# Insperino_-_Ver_1_0.net
KiCad netlist of a schematic drawn in EAGLE
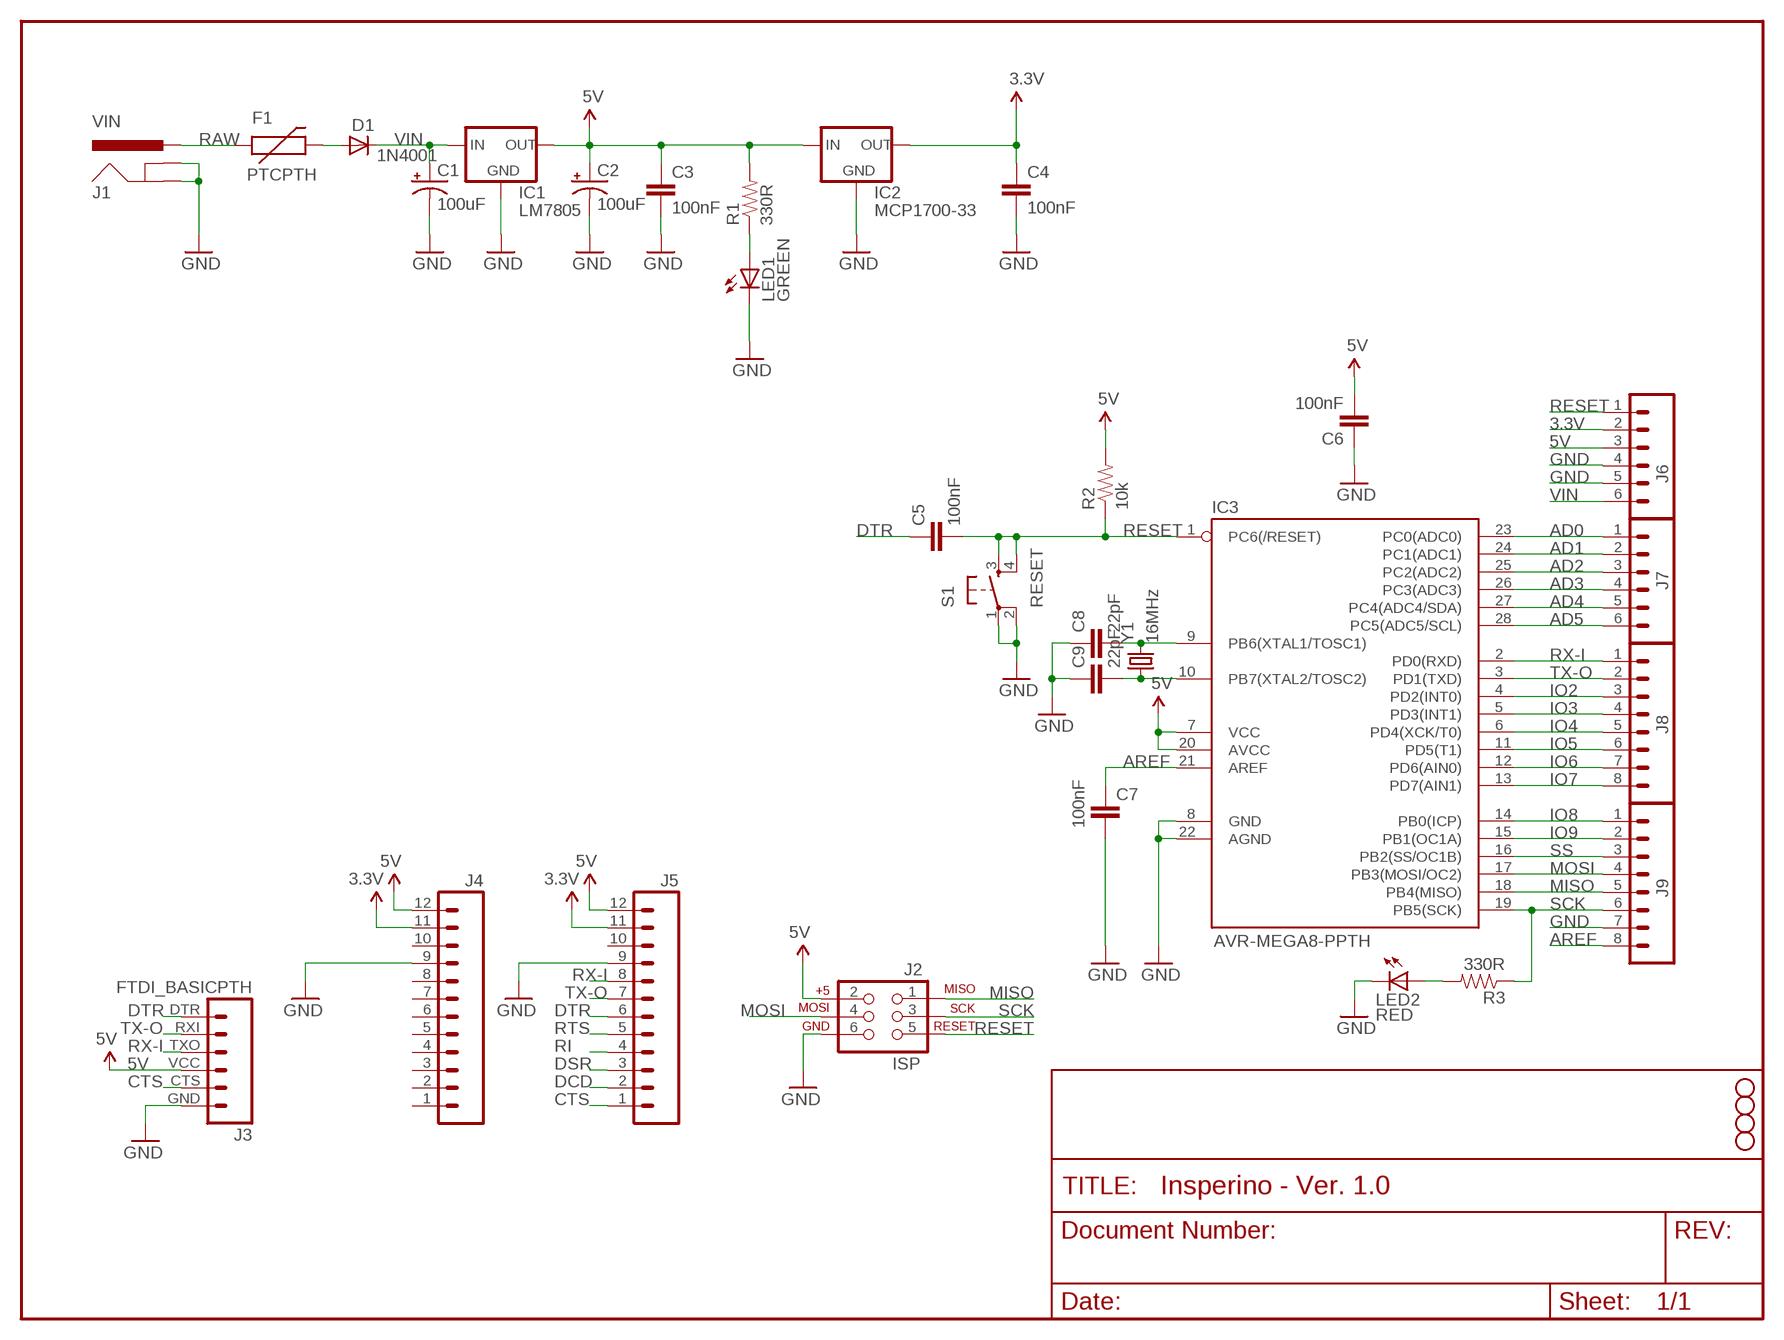
[diagram p0: schematic, sheet 1]

(export (version "E")
  (design (tool "Eeschema 10.0.6"))
  (components
    (comp (ref "C1")
      (value "100uF")
      (footprint "eagle-import:CPOL-RADIAL-100UF-25V")
      (libsource (lib "eagle-import") (part "CAP_POLPTH1"))
    )
    (comp (ref "C2")
      (value "100uF")
      (footprint "eagle-import:CPOL-RADIAL-100UF-25V")
      (libsource (lib "eagle-import") (part "CAP_POLPTH1"))
    )
    (comp (ref "C3")
      (value "100nF")
      (footprint "eagle-import:CAP-PTH-SMALL2")
      (libsource (lib "eagle-import") (part "CAPPTH2"))
    )
    (comp (ref "C4")
      (value "100nF")
      (footprint "eagle-import:CAP-PTH-SMALL2")
      (libsource (lib "eagle-import") (part "CAPPTH2"))
    )
    (comp (ref "C5")
      (value "100nF")
      (footprint "eagle-import:CAP-PTH-SMALL2")
      (libsource (lib "eagle-import") (part "CAPPTH2"))
    )
    (comp (ref "C6")
      (value "100nF")
      (footprint "eagle-import:CAP-PTH-SMALL2")
      (libsource (lib "eagle-import") (part "CAPPTH2"))
    )
    (comp (ref "C7")
      (value "100nF")
      (footprint "eagle-import:CAP-PTH-SMALL2")
      (libsource (lib "eagle-import") (part "CAPPTH2"))
    )
    (comp (ref "C8")
      (value "22pF")
      (footprint "eagle-import:CAP-PTH-SMALL2")
      (libsource (lib "eagle-import") (part "CAPPTH2"))
    )
    (comp (ref "C9")
      (value "22pF")
      (footprint "eagle-import:CAP-PTH-SMALL2")
      (libsource (lib "eagle-import") (part "CAPPTH2"))
    )
    (comp (ref "D1")
      (value "1N4001")
      (footprint "eagle-import:DIODE-1N4001")
      (libsource (lib "eagle-import") (part "DIODEPTH"))
    )
    (comp (ref "F1")
      (value "PTCPTH")
      (footprint "eagle-import:PTC")
      (libsource (lib "eagle-import") (part "PTCPTH"))
    )
    (comp (ref "IC1")
      (value "LM7805")
      (footprint "eagle-import:TO-220-ALT")
      (libsource (lib "eagle-import") (part "V_REG_78XX-TO-220"))
    )
    (comp (ref "IC2")
      (value "MCP1700-33")
      (footprint "eagle-import:TO-92")
      (libsource (lib "eagle-import") (part "V_REG_78XXTO-92"))
    )
    (comp (ref "IC3")
      (value "AVR-MEGA8-PPTH")
      (footprint "eagle-import:DIL28-3")
      (libsource (lib "eagle-import") (part "AVR-MEGA8-PPTH"))
    )
    (comp (ref "J1")
      (value "VIN")
      (footprint "eagle-import:POWER_JACK_PTH_LOCK")
      (libsource (lib "eagle-import") (part "POWER_JACKPTH_LOCK"))
    )
    (comp (ref "J2")
      (value "ISP")
      (footprint "eagle-import:2X3")
      (libsource (lib "eagle-import") (part "AVR_SPI_PRG_6PTH"))
    )
    (comp (ref "J3")
      (value "FTDI_BASICPTH")
      (footprint "eagle-import:FTDI_BASIC")
      (libsource (lib "eagle-import") (part "FTDI_BASICPTH"))
    )
    (comp (ref "J4")
      (value "M12PTH")
      (footprint "eagle-import:1X12")
      (libsource (lib "eagle-import") (part "M12PTH"))
    )
    (comp (ref "J5")
      (value "M12PTH")
      (footprint "eagle-import:1X12")
      (libsource (lib "eagle-import") (part "M12PTH"))
    )
    (comp (ref "J6")
      (value "M06SIP")
      (footprint "eagle-import:1X06")
      (libsource (lib "eagle-import") (part "M06SIP"))
    )
    (comp (ref "J7")
      (value "M06SIP")
      (footprint "eagle-import:1X06")
      (libsource (lib "eagle-import") (part "M06SIP"))
    )
    (comp (ref "J8")
      (value "M081X08")
      (footprint "eagle-import:1X08")
      (libsource (lib "eagle-import") (part "M081X08"))
    )
    (comp (ref "J9")
      (value "M081X08")
      (footprint "eagle-import:1X08")
      (libsource (lib "eagle-import") (part "M081X08"))
    )
    (comp (ref "JP3")
      (value "STAND-OFF")
      (footprint "eagle-import:STAND-OFF")
      (libsource (lib "eagle-import") (part "STAND-OFF"))
    )
    (comp (ref "JP4")
      (value "STAND-OFF")
      (footprint "eagle-import:STAND-OFF")
      (libsource (lib "eagle-import") (part "STAND-OFF"))
    )
    (comp (ref "JP5")
      (value "STAND-OFF")
      (footprint "eagle-import:STAND-OFF")
      (libsource (lib "eagle-import") (part "STAND-OFF"))
    )
    (comp (ref "JP6")
      (value "STAND-OFF")
      (footprint "eagle-import:STAND-OFF")
      (libsource (lib "eagle-import") (part "STAND-OFF"))
    )
    (comp (ref "LED1")
      (value "GREEN")
      (footprint "eagle-import:LED5MM")
      (libsource (lib "eagle-import") (part "LED5MM"))
    )
    (comp (ref "LED2")
      (value "RED")
      (footprint "eagle-import:LED5MM")
      (libsource (lib "eagle-import") (part "LED5MM"))
    )
    (comp (ref "R1")
      (value "330R")
      (footprint "eagle-import:AXIAL-0.3")
      (libsource (lib "eagle-import") (part "RESISTORAXIAL-0.3"))
    )
    (comp (ref "R2")
      (value "10k")
      (footprint "eagle-import:AXIAL-0.3")
      (libsource (lib "eagle-import") (part "RESISTORAXIAL-0.3"))
    )
    (comp (ref "R3")
      (value "330R")
      (footprint "eagle-import:AXIAL-0.3")
      (libsource (lib "eagle-import") (part "RESISTORAXIAL-0.3"))
    )
    (comp (ref "S1")
      (value "RESET")
      (footprint "eagle-import:TACTILE-PTH")
      (libsource (lib "eagle-import") (part "TAC_SWITCHPTH"))
    )
    (comp (ref "Y1")
      (value "16MHz")
      (footprint "eagle-import:HC49US")
      (libsource (lib "eagle-import") (part "CRYSTALHC49US"))
    )
  )
  (nets
    (net (code "1") (name "/AD0") (class "Default")
      (node (ref "IC3") (pin "23") (pinfunction "PC0(ADC0)_23") (pintype "bidirectional"))
      (node (ref "J7") (pin "1") (pinfunction "1_1") (pintype "passive"))
    )
    (net (code "2") (name "/AD1") (class "Default")
      (node (ref "IC3") (pin "24") (pinfunction "PC1(ADC1)_24") (pintype "bidirectional"))
      (node (ref "J7") (pin "2") (pinfunction "2_2") (pintype "passive"))
    )
    (net (code "3") (name "/AD2") (class "Default")
      (node (ref "IC3") (pin "25") (pinfunction "PC2(ADC2)_25") (pintype "bidirectional"))
      (node (ref "J7") (pin "3") (pinfunction "3_3") (pintype "passive"))
    )
    (net (code "4") (name "/AD3") (class "Default")
      (node (ref "IC3") (pin "26") (pinfunction "PC3(ADC3)_26") (pintype "bidirectional"))
      (node (ref "J7") (pin "4") (pinfunction "4_4") (pintype "passive"))
    )
    (net (code "5") (name "/AD4") (class "Default")
      (node (ref "IC3") (pin "27") (pinfunction "PC4(ADC4/SDA)_27") (pintype "bidirectional"))
      (node (ref "J7") (pin "5") (pinfunction "5_5") (pintype "passive"))
    )
    (net (code "6") (name "/AD5") (class "Default")
      (node (ref "IC3") (pin "28") (pinfunction "PC5(ADC5/SCL)_28") (pintype "bidirectional"))
      (node (ref "J7") (pin "6") (pinfunction "6_6") (pintype "passive"))
    )
    (net (code "7") (name "/AREF") (class "Default")
      (node (ref "C7") (pin "1") (pinfunction "1_1") (pintype "passive"))
      (node (ref "IC3") (pin "21") (pinfunction "AREF_21") (pintype "bidirectional"))
      (node (ref "J9") (pin "8") (pinfunction "8_8") (pintype "passive"))
    )
    (net (code "8") (name "/CTS") (class "Default")
      (node (ref "J3") (pin "CTS") (pinfunction "5_CTS") (pintype "passive"))
      (node (ref "J5") (pin "1") (pinfunction "1_1") (pintype "passive"))
    )
    (net (code "9") (name "/DCD") (class "Default")
      (node (ref "J5") (pin "2") (pinfunction "2_2") (pintype "passive"))
    )
    (net (code "10") (name "/DSR") (class "Default")
      (node (ref "J5") (pin "3") (pinfunction "3_3") (pintype "passive"))
    )
    (net (code "11") (name "/DTR") (class "Default")
      (node (ref "C5") (pin "1") (pinfunction "1_1") (pintype "passive"))
      (node (ref "J3") (pin "DTR") (pinfunction "1_DTR") (pintype "passive"))
      (node (ref "J5") (pin "6") (pinfunction "6_6") (pintype "passive"))
    )
    (net (code "12") (name "/IO2") (class "Default")
      (node (ref "IC3") (pin "4") (pinfunction "PD2(INT0)_4") (pintype "bidirectional"))
      (node (ref "J8") (pin "3") (pinfunction "3_3") (pintype "passive"))
    )
    (net (code "13") (name "/IO3") (class "Default")
      (node (ref "IC3") (pin "5") (pinfunction "PD3(INT1)_5") (pintype "bidirectional"))
      (node (ref "J8") (pin "4") (pinfunction "4_4") (pintype "passive"))
    )
    (net (code "14") (name "/IO4") (class "Default")
      (node (ref "IC3") (pin "6") (pinfunction "PD4(XCK/T0)_6") (pintype "bidirectional"))
      (node (ref "J8") (pin "5") (pinfunction "5_5") (pintype "passive"))
    )
    (net (code "15") (name "/IO5") (class "Default")
      (node (ref "IC3") (pin "11") (pinfunction "PD5(T1)_11") (pintype "bidirectional"))
      (node (ref "J8") (pin "6") (pinfunction "6_6") (pintype "passive"))
    )
    (net (code "16") (name "/IO6") (class "Default")
      (node (ref "IC3") (pin "12") (pinfunction "PD6(AIN0)_12") (pintype "bidirectional"))
      (node (ref "J8") (pin "7") (pinfunction "7_7") (pintype "passive"))
    )
    (net (code "17") (name "/IO7") (class "Default")
      (node (ref "IC3") (pin "13") (pinfunction "PD7(AIN1)_13") (pintype "bidirectional"))
      (node (ref "J8") (pin "8") (pinfunction "8_8") (pintype "passive"))
    )
    (net (code "18") (name "/IO8") (class "Default")
      (node (ref "IC3") (pin "14") (pinfunction "PB0(ICP)_14") (pintype "bidirectional"))
      (node (ref "J9") (pin "1") (pinfunction "1_1") (pintype "passive"))
    )
    (net (code "19") (name "/IO9") (class "Default")
      (node (ref "IC3") (pin "15") (pinfunction "PB1(OC1A)_15") (pintype "bidirectional"))
      (node (ref "J9") (pin "2") (pinfunction "2_2") (pintype "passive"))
    )
    (net (code "20") (name "/MISO") (class "Default")
      (node (ref "IC3") (pin "18") (pinfunction "PB4(MISO)_18") (pintype "bidirectional"))
      (node (ref "J2") (pin "1") (pinfunction "1_1") (pintype "passive"))
      (node (ref "J9") (pin "5") (pinfunction "5_5") (pintype "passive"))
    )
    (net (code "21") (name "/MOSI") (class "Default")
      (node (ref "IC3") (pin "17") (pinfunction "PB3(MOSI/OC2)_17") (pintype "bidirectional"))
      (node (ref "J2") (pin "4") (pinfunction "4_4") (pintype "passive"))
      (node (ref "J9") (pin "4") (pinfunction "4_4") (pintype "passive"))
    )
    (net (code "22") (name "/RAW") (class "Default")
      (node (ref "F1") (pin "P$1") (pinfunction "1_P$1") (pintype "bidirectional"))
      (node (ref "J1") (pin "PWR") (pinfunction "PWR_PWR") (pintype "bidirectional"))
    )
    (net (code "23") (name "/RESET") (class "Default")
      (node (ref "C5") (pin "2") (pinfunction "2_2") (pintype "passive"))
      (node (ref "IC3") (pin "1") (pinfunction "PC6(/RESET)_1") (pintype "bidirectional"))
      (node (ref "J2") (pin "5") (pinfunction "5_5") (pintype "passive"))
      (node (ref "J6") (pin "1") (pinfunction "1_1") (pintype "passive"))
      (node (ref "R2") (pin "P$1") (pinfunction "1_P$1") (pintype "passive"))
      (node (ref "S1") (pin "3") (pinfunction "3_3") (pintype "passive"))
      (node (ref "S1") (pin "4") (pinfunction "4_4") (pintype "passive"))
    )
    (net (code "24") (name "/RI") (class "Default")
      (node (ref "J5") (pin "4") (pinfunction "4_4") (pintype "passive"))
    )
    (net (code "25") (name "/RTS") (class "Default")
      (node (ref "J5") (pin "5") (pinfunction "5_5") (pintype "passive"))
    )
    (net (code "26") (name "/RX-I") (class "Default")
      (node (ref "IC3") (pin "2") (pinfunction "PD0(RXD)_2") (pintype "bidirectional"))
      (node (ref "J3") (pin "TXO") (pinfunction "3_TXO") (pintype "passive"))
      (node (ref "J5") (pin "8") (pinfunction "8_8") (pintype "passive"))
      (node (ref "J8") (pin "1") (pinfunction "1_1") (pintype "passive"))
    )
    (net (code "27") (name "/SCK") (class "Default")
      (node (ref "IC3") (pin "19") (pinfunction "PB5(SCK)_19") (pintype "bidirectional"))
      (node (ref "J2") (pin "3") (pinfunction "3_3") (pintype "passive"))
      (node (ref "J9") (pin "6") (pinfunction "6_6") (pintype "passive"))
      (node (ref "R3") (pin "P$1") (pinfunction "1_P$1") (pintype "passive"))
    )
    (net (code "28") (name "/SS") (class "Default")
      (node (ref "IC3") (pin "16") (pinfunction "PB2(SS/OC1B)_16") (pintype "bidirectional"))
      (node (ref "J9") (pin "3") (pinfunction "3_3") (pintype "passive"))
    )
    (net (code "29") (name "/TX-O") (class "Default")
      (node (ref "IC3") (pin "3") (pinfunction "PD1(TXD)_3") (pintype "bidirectional"))
      (node (ref "J3") (pin "RXI") (pinfunction "2_RXI") (pintype "passive"))
      (node (ref "J5") (pin "7") (pinfunction "7_7") (pintype "passive"))
      (node (ref "J8") (pin "2") (pinfunction "2_2") (pintype "passive"))
    )
    (net (code "30") (name "/VIN") (class "Default")
      (node (ref "C1") (pin "1") (pinfunction "+_1") (pintype "passive"))
      (node (ref "D1") (pin "C") (pinfunction "C_C") (pintype "passive"))
      (node (ref "IC1") (pin "IN") (pinfunction "IN_IN") (pintype "input"))
      (node (ref "J6") (pin "6") (pinfunction "6_6") (pintype "passive"))
    )
    (net (code "31") (name "3.3V") (class "Default")
      (node (ref "C4") (pin "1") (pinfunction "1_1") (pintype "passive"))
      (node (ref "IC2") (pin "3") (pinfunction "OUT_3") (pintype "output"))
      (node (ref "J4") (pin "11") (pinfunction "11_11") (pintype "passive"))
      (node (ref "J5") (pin "11") (pinfunction "11_11") (pintype "passive"))
      (node (ref "J6") (pin "2") (pinfunction "2_2") (pintype "passive"))
    )
    (net (code "32") (name "5V") (class "Default")
      (node (ref "C2") (pin "1") (pinfunction "+_1") (pintype "passive"))
      (node (ref "C3") (pin "1") (pinfunction "1_1") (pintype "passive"))
      (node (ref "C6") (pin "2") (pinfunction "2_2") (pintype "passive"))
      (node (ref "IC1") (pin "OUT") (pinfunction "OUT_OUT") (pintype "output"))
      (node (ref "IC2") (pin "2") (pinfunction "IN_2") (pintype "input"))
      (node (ref "IC3") (pin "20") (pinfunction "AVCC_20") (pintype "bidirectional"))
      (node (ref "IC3") (pin "7") (pinfunction "VCC_7") (pintype "bidirectional"))
      (node (ref "J2") (pin "2") (pinfunction "2_2") (pintype "passive"))
      (node (ref "J3") (pin "VCC") (pinfunction "4_VCC") (pintype "passive"))
      (node (ref "J4") (pin "12") (pinfunction "12_12") (pintype "passive"))
      (node (ref "J5") (pin "12") (pinfunction "12_12") (pintype "passive"))
      (node (ref "J6") (pin "3") (pinfunction "3_3") (pintype "passive"))
      (node (ref "R1") (pin "P$2") (pinfunction "2_P$2") (pintype "passive"))
      (node (ref "R2") (pin "P$2") (pinfunction "2_P$2") (pintype "passive"))
    )
    (net (code "33") (name "GND") (class "Default")
      (node (ref "C1") (pin "2") (pinfunction "-_2") (pintype "passive"))
      (node (ref "C2") (pin "2") (pinfunction "-_2") (pintype "passive"))
      (node (ref "C3") (pin "2") (pinfunction "2_2") (pintype "passive"))
      (node (ref "C4") (pin "2") (pinfunction "2_2") (pintype "passive"))
      (node (ref "C6") (pin "1") (pinfunction "1_1") (pintype "passive"))
      (node (ref "C7") (pin "2") (pinfunction "2_2") (pintype "passive"))
      (node (ref "C8") (pin "1") (pinfunction "1_1") (pintype "passive"))
      (node (ref "C9") (pin "1") (pinfunction "1_1") (pintype "passive"))
      (node (ref "IC1") (pin "GND") (pinfunction "GND_GND") (pintype "input"))
      (node (ref "IC2") (pin "1") (pinfunction "GND_1") (pintype "input"))
      (node (ref "IC3") (pin "22") (pinfunction "AGND_22") (pintype "bidirectional"))
      (node (ref "IC3") (pin "8") (pinfunction "GND_8") (pintype "bidirectional"))
      (node (ref "J1") (pin "GND") (pinfunction "GND_GND") (pintype "bidirectional"))
      (node (ref "J1") (pin "GNDBREAK") (pinfunction "GNDBREAK_GNDBREAK") (pintype "bidirectional"))
      (node (ref "J2") (pin "6") (pinfunction "6_6") (pintype "passive"))
      (node (ref "J3") (pin "GND") (pinfunction "6_GND") (pintype "passive"))
      (node (ref "J4") (pin "9") (pinfunction "9_9") (pintype "passive"))
      (node (ref "J5") (pin "9") (pinfunction "9_9") (pintype "passive"))
      (node (ref "J6") (pin "4") (pinfunction "4_4") (pintype "passive"))
      (node (ref "J6") (pin "5") (pinfunction "5_5") (pintype "passive"))
      (node (ref "J9") (pin "7") (pinfunction "7_7") (pintype "passive"))
      (node (ref "LED1") (pin "K") (pinfunction "C_K") (pintype "passive"))
      (node (ref "LED2") (pin "K") (pinfunction "C_K") (pintype "passive"))
      (node (ref "S1") (pin "1") (pinfunction "1_1") (pintype "passive"))
      (node (ref "S1") (pin "2") (pinfunction "2_2") (pintype "passive"))
    )
    (net (code "34") (name "Net-(F1-2)") (class "Default")
      (node (ref "D1") (pin "A") (pinfunction "A_A") (pintype "passive"))
      (node (ref "F1") (pin "P$2") (pinfunction "2_P$2") (pintype "bidirectional"))
    )
    (net (code "35") (name "Net-(IC3-PB6(XTAL1{slash}TOSC1))") (class "Default")
      (node (ref "C8") (pin "2") (pinfunction "2_2") (pintype "passive"))
      (node (ref "IC3") (pin "9") (pinfunction "PB6(XTAL1/TOSC1)_9") (pintype "bidirectional"))
      (node (ref "Y1") (pin "2") (pinfunction "2_2") (pintype "passive"))
    )
    (net (code "36") (name "Net-(IC3-PB7(XTAL2{slash}TOSC2))") (class "Default")
      (node (ref "C9") (pin "2") (pinfunction "2_2") (pintype "passive"))
      (node (ref "IC3") (pin "10") (pinfunction "PB7(XTAL2/TOSC2)_10") (pintype "bidirectional"))
      (node (ref "Y1") (pin "1") (pinfunction "1_1") (pintype "passive"))
    )
    (net (code "37") (name "Net-(R1-1)") (class "Default")
      (node (ref "LED1") (pin "A") (pinfunction "A_A") (pintype "passive"))
      (node (ref "R1") (pin "P$1") (pinfunction "1_P$1") (pintype "passive"))
    )
    (net (code "38") (name "Net-(R3-2)") (class "Default")
      (node (ref "LED2") (pin "A") (pinfunction "A_A") (pintype "passive"))
      (node (ref "R3") (pin "P$2") (pinfunction "2_P$2") (pintype "passive"))
    )
    (net (code "39") (name "unconnected-(J4-Pad1)") (class "Default")
      (node (ref "J4") (pin "1") (pinfunction "1_1") (pintype "passive"))
    )
    (net (code "40") (name "unconnected-(J4-Pad2)") (class "Default")
      (node (ref "J4") (pin "2") (pinfunction "2_2") (pintype "passive"))
    )
    (net (code "41") (name "unconnected-(J4-Pad3)") (class "Default")
      (node (ref "J4") (pin "3") (pinfunction "3_3") (pintype "passive"))
    )
    (net (code "42") (name "unconnected-(J4-Pad4)") (class "Default")
      (node (ref "J4") (pin "4") (pinfunction "4_4") (pintype "passive"))
    )
    (net (code "43") (name "unconnected-(J4-Pad5)") (class "Default")
      (node (ref "J4") (pin "5") (pinfunction "5_5") (pintype "passive"))
    )
    (net (code "44") (name "unconnected-(J4-Pad6)") (class "Default")
      (node (ref "J4") (pin "6") (pinfunction "6_6") (pintype "passive"))
    )
    (net (code "45") (name "unconnected-(J4-Pad7)") (class "Default")
      (node (ref "J4") (pin "7") (pinfunction "7_7") (pintype "passive"))
    )
    (net (code "46") (name "unconnected-(J4-Pad8)") (class "Default")
      (node (ref "J4") (pin "8") (pinfunction "8_8") (pintype "passive"))
    )
    (net (code "47") (name "unconnected-(J4-Pad10)") (class "Default")
      (node (ref "J4") (pin "10") (pinfunction "10_10") (pintype "passive"))
    )
    (net (code "48") (name "unconnected-(J5-Pad10)") (class "Default")
      (node (ref "J5") (pin "10") (pinfunction "10_10") (pintype "passive"))
    )
  )
)
